# AirU_PoE.net
KiCad netlist of a schematic drawn in EAGLE
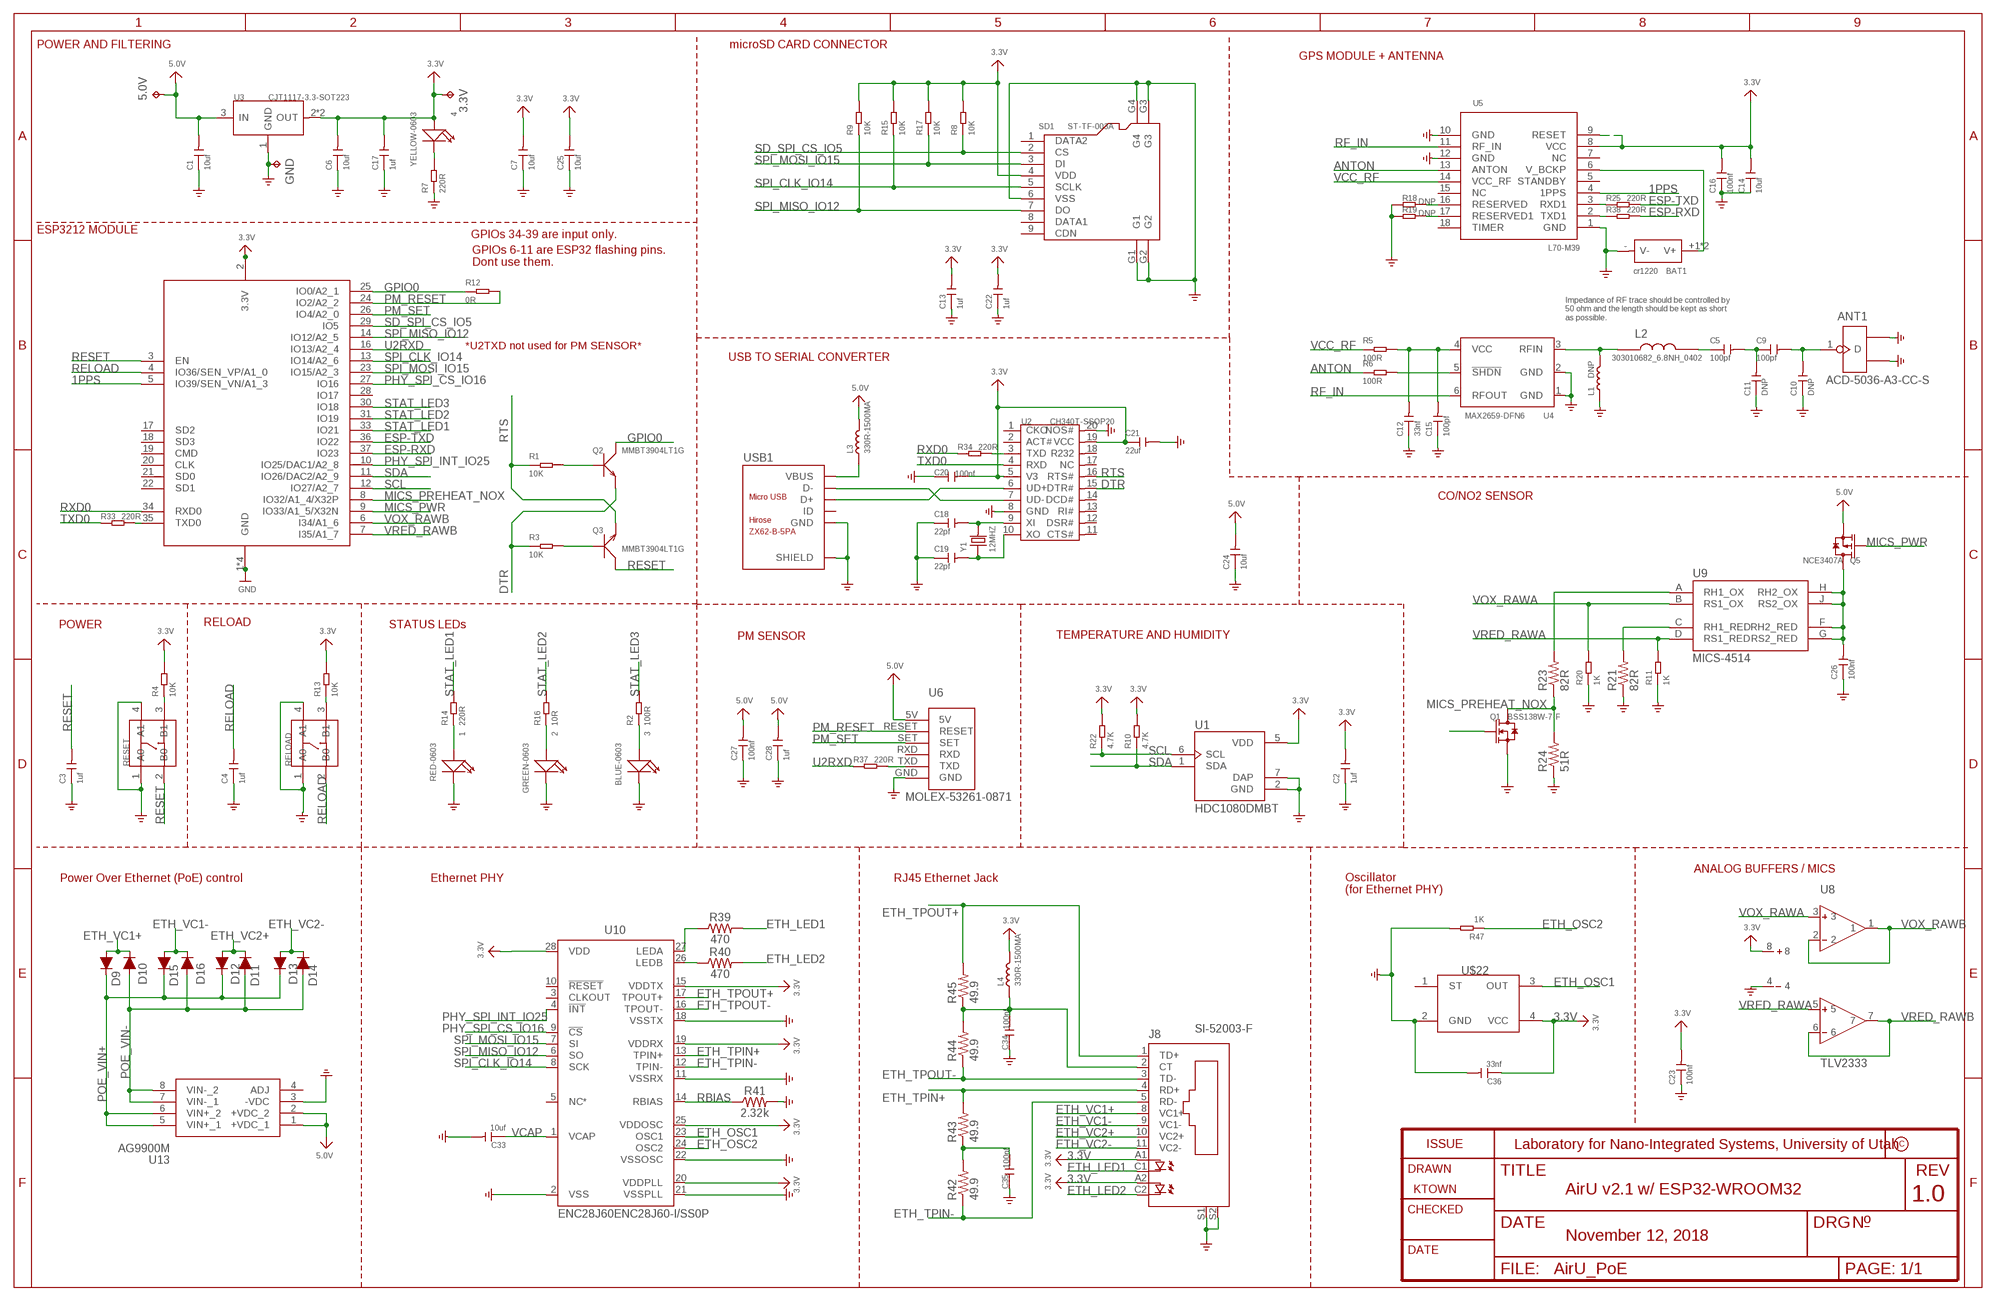
[diagram p0: schematic, sheet 1]

(export (version "E")
  (design (tool "Eeschema 10.0.6"))
  (components
    (comp (ref "1")
      (value "RED-0603")
      (footprint "eagle-import:LED-0603")
      (fields (field (name "MPN") "19-217-R6C-AL1M2VY-3T"))
      (libsource (lib "eagle-import") (part "LED-SMD-RED-DIFFUSED(0603)"))
    )
    (comp (ref "2")
      (value "GREEN-0603")
      (footprint "eagle-import:LED-0603")
      (fields (field (name "MPN") "19-217-G7C-AN1P2-3T"))
      (libsource (lib "eagle-import") (part "SMD-LED-CLEAR-GREEN(0603)"))
    )
    (comp (ref "3")
      (value "BLUE-0603")
      (footprint "eagle-import:LED-0603")
      (fields (field (name "MPN") "19-217-BHC-ZL1M2RY-3T"))
      (libsource (lib "eagle-import") (part "SMD-LED-CLEAR-BLUE(0603)"))
    )
    (comp (ref "3.3V")
      (value "TPTP20SQ")
      (footprint "eagle-import:TP20SQ")
      (libsource (lib "eagle-import") (part "TPTP20SQ"))
    )
    (comp (ref "4")
      (value "YELLOW-0603")
      (footprint "eagle-import:LED-0603")
      (fields (field (name "MPN") "19-217-Y5C-AM1N1VY-3T"))
      (libsource (lib "eagle-import") (part "SMD-LED-CLEAR-YELLOW(0603)"))
    )
    (comp (ref "5.0V")
      (value "TPTP20SQ")
      (footprint "eagle-import:TP20SQ")
      (libsource (lib "eagle-import") (part "TPTP20SQ"))
    )
    (comp (ref "ANT1")
      (value "ACD-5036-A3-CC-S")
      (footprint "eagle-import:ANT3-SMD-5.2X3.7X0.7MM")
      (libsource (lib "eagle-import") (part "ANTENNA-ACD5036"))
    )
    (comp (ref "BAT1")
      (value "cr1220")
      (footprint "eagle-import:BAT2P-13.5-CR1220")
      (libsource (lib "eagle-import") (part "DIP-BATTERY-CELL-HOLDER(1220)"))
    )
    (comp (ref "C1")
      (value "10uf")
      (footprint "eagle-import:C0603")
      (fields (field (name "MPN") "CC0603KRX5R6BB106"))
      (libsource (lib "eagle-import") (part "CERAMIC-10UF-10V-10%-X5R(0603)"))
    )
    (comp (ref "C2")
      (value "1uf")
      (footprint "eagle-import:C0603")
      (fields (field (name "MPN") "CC0603KRX7R8BB105"))
      (libsource (lib "eagle-import") (part "CERAMIC-1UF-25V-10%-X7R(0603)"))
    )
    (comp (ref "C3")
      (value "1uf")
      (footprint "eagle-import:C0603")
      (fields (field (name "MPN") "CC0603KRX7R8BB105"))
      (libsource (lib "eagle-import") (part "CERAMIC-1UF-25V-10%-X7R(0603)"))
    )
    (comp (ref "C4")
      (value "1uf")
      (footprint "eagle-import:C0603")
      (fields (field (name "MPN") "CC0603KRX7R8BB105"))
      (libsource (lib "eagle-import") (part "CERAMIC-1UF-25V-10%-X7R(0603)"))
    )
    (comp (ref "C5")
      (value "100pf")
      (footprint "eagle-import:C0603")
      (fields (field (name "MPN") "CC0603JRNPO9BN101"))
      (libsource (lib "eagle-import") (part "CERAMIC-100PF-50V-5%-NPO(0603)"))
    )
    (comp (ref "C6")
      (value "10uf")
      (footprint "eagle-import:C0603")
      (fields (field (name "MPN") "CC0603KRX5R6BB106"))
      (libsource (lib "eagle-import") (part "CERAMIC-10UF-10V-10%-X5R(0603)"))
    )
    (comp (ref "C7")
      (value "10uf")
      (footprint "eagle-import:C0603")
      (fields (field (name "MPN") "CC0603KRX5R6BB106"))
      (libsource (lib "eagle-import") (part "CERAMIC-10UF-10V-10%-X5R(0603)"))
    )
    (comp (ref "C9")
      (value "100pf")
      (footprint "eagle-import:C0603")
      (fields (field (name "MPN") "CC0603JRNPO9BN101"))
      (libsource (lib "eagle-import") (part "CERAMIC-100PF-50V-5%-NPO(0603)"))
    )
    (comp (ref "C10")
      (value "DNP")
      (footprint "eagle-import:C0603")
      (fields (field (name "MPN") "CC0603JRNPO9BN101"))
      (libsource (lib "eagle-import") (part "CERAMIC-100PF-50V-5%-NPO(0603)"))
    )
    (comp (ref "C11")
      (value "DNP")
      (footprint "eagle-import:C0603")
      (fields (field (name "MPN") "CC0603JRNPO9BN101"))
      (libsource (lib "eagle-import") (part "CERAMIC-100PF-50V-5%-NPO(0603)"))
    )
    (comp (ref "C12")
      (value "33nf")
      (footprint "eagle-import:C0603")
      (fields (field (name "MPN") "CC0603KRX7R9BB333"))
      (libsource (lib "eagle-import") (part "CERAMIC-33NF-50V-10%-X7R(0603)"))
    )
    (comp (ref "C13")
      (value "1uf")
      (footprint "eagle-import:C0603")
      (fields (field (name "MPN") "CC0603KRX7R8BB105"))
      (libsource (lib "eagle-import") (part "CERAMIC-1UF-25V-10%-X7R(0603)"))
    )
    (comp (ref "C14")
      (value "10uf")
      (footprint "eagle-import:C0603")
      (fields (field (name "MPN") "CC0603KRX5R6BB106"))
      (libsource (lib "eagle-import") (part "CERAMIC-10UF-10V-10%-X5R(0603)"))
    )
    (comp (ref "C15")
      (value "100pf")
      (footprint "eagle-import:C0603")
      (fields (field (name "MPN") "CC0603JRNPO9BN101"))
      (libsource (lib "eagle-import") (part "CERAMIC-100PF-50V-5%-NPO(0603)"))
    )
    (comp (ref "C16")
      (value "100nf")
      (footprint "eagle-import:C0603")
      (fields (field (name "MPN") "CC0603KRX7R9BB104"))
      (libsource (lib "eagle-import") (part "CERAMIC-100NF-50V-10%-X7R(0603)"))
    )
    (comp (ref "C17")
      (value "1uf")
      (footprint "eagle-import:C0603")
      (fields (field (name "MPN") "CC0603KRX7R8BB105"))
      (libsource (lib "eagle-import") (part "CERAMIC-1UF-25V-10%-X7R(0603)"))
    )
    (comp (ref "C18")
      (value "22pf")
      (footprint "eagle-import:C0603")
      (fields (field (name "MPN") "CC0603JRNPO9BN220"))
      (libsource (lib "eagle-import") (part "CERAMIC-22PF-50V-5%-NPO(0603)"))
    )
    (comp (ref "C19")
      (value "22pf")
      (footprint "eagle-import:C0603")
      (fields (field (name "MPN") "CC0603JRNPO9BN220"))
      (libsource (lib "eagle-import") (part "CERAMIC-22PF-50V-5%-NPO(0603)"))
    )
    (comp (ref "C20")
      (value "100nf")
      (footprint "eagle-import:C0603")
      (fields (field (name "MPN") "CC0603KRX7R9BB104"))
      (libsource (lib "eagle-import") (part "CERAMIC-100NF-50V-10%-X7R(0603)"))
    )
    (comp (ref "C21")
      (value "22uf")
      (footprint "eagle-import:C0805")
      (fields (field (name "MPN") "CC0805MKX5R5BB226"))
      (libsource (lib "eagle-import") (part "CERAMIC-22UF-6.3V-20%-X5R(0805)"))
    )
    (comp (ref "C22")
      (value "1uf")
      (footprint "eagle-import:C0603")
      (fields (field (name "MPN") "CC0603KRX7R8BB105"))
      (libsource (lib "eagle-import") (part "CERAMIC-1UF-25V-10%-X7R(0603)"))
    )
    (comp (ref "C23")
      (value "100nf")
      (footprint "eagle-import:C0603")
      (fields (field (name "MPN") "CC0603KRX7R9BB104"))
      (libsource (lib "eagle-import") (part "CERAMIC-100NF-50V-10%-X7R(0603)"))
    )
    (comp (ref "C24")
      (value "10uf")
      (footprint "eagle-import:C0603")
      (fields (field (name "MPN") "CC0603KRX5R6BB106"))
      (libsource (lib "eagle-import") (part "CERAMIC-10UF-10V-10%-X5R(0603)"))
    )
    (comp (ref "C25")
      (value "10uf")
      (footprint "eagle-import:C0603")
      (fields (field (name "MPN") "CC0603KRX5R6BB106"))
      (libsource (lib "eagle-import") (part "CERAMIC-10UF-10V-10%-X5R(0603)"))
    )
    (comp (ref "C26")
      (value "100nf")
      (footprint "eagle-import:C0603")
      (fields (field (name "MPN") "CC0603KRX7R9BB104"))
      (libsource (lib "eagle-import") (part "CERAMIC-100NF-50V-10%-X7R(0603)"))
    )
    (comp (ref "C27")
      (value "100nf")
      (footprint "eagle-import:C0603")
      (fields (field (name "MPN") "CC0603KRX7R9BB104"))
      (libsource (lib "eagle-import") (part "CERAMIC-100NF-50V-10%-X7R(0603)"))
    )
    (comp (ref "C28")
      (value "1uf")
      (footprint "eagle-import:C0603")
      (fields (field (name "MPN") "CC0603KRX7R8BB105"))
      (libsource (lib "eagle-import") (part "CERAMIC-1UF-25V-10%-X7R(0603)"))
    )
    (comp (ref "C33")
      (value "10uf")
      (footprint "eagle-import:C0603")
      (fields (field (name "MPN") "CC0603KRX5R6BB106"))
      (libsource (lib "eagle-import") (part "CERAMIC-10UF-10V-10%-X5R(0603)"))
    )
    (comp (ref "C34")
      (value "100nf")
      (footprint "eagle-import:C0603")
      (fields (field (name "MPN") "CC0603KRX7R9BB104"))
      (libsource (lib "eagle-import") (part "CERAMIC-100NF-50V-10%-X7R(0603)"))
    )
    (comp (ref "C35")
      (value "100nf")
      (footprint "eagle-import:C0603")
      (fields (field (name "MPN") "CC0603KRX7R9BB104"))
      (libsource (lib "eagle-import") (part "CERAMIC-100NF-50V-10%-X7R(0603)"))
    )
    (comp (ref "C36")
      (value "33nf")
      (footprint "eagle-import:C0603")
      (fields (field (name "MPN") "CC0603KRX7R9BB333"))
      (libsource (lib "eagle-import") (part "CERAMIC-33NF-50V-10%-X7R(0603)"))
    )
    (comp (ref "D9")
      (value "250mA/100V")
      (footprint "eagle-import:SOD-323")
      (libsource (lib "eagle-import") (part "DIODE-BAS16J"))
    )
    (comp (ref "D10")
      (value "250mA/100V")
      (footprint "eagle-import:SOD-323")
      (libsource (lib "eagle-import") (part "DIODE-BAS16J"))
    )
    (comp (ref "D11")
      (value "250mA/100V")
      (footprint "eagle-import:SOD-323")
      (libsource (lib "eagle-import") (part "DIODE-BAS16J"))
    )
    (comp (ref "D12")
      (value "250mA/100V")
      (footprint "eagle-import:SOD-323")
      (libsource (lib "eagle-import") (part "DIODE-BAS16J"))
    )
    (comp (ref "D13")
      (value "250mA/100V")
      (footprint "eagle-import:SOD-323")
      (libsource (lib "eagle-import") (part "DIODE-BAS16J"))
    )
    (comp (ref "D14")
      (value "250mA/100V")
      (footprint "eagle-import:SOD-323")
      (libsource (lib "eagle-import") (part "DIODE-BAS16J"))
    )
    (comp (ref "D15")
      (value "250mA/100V")
      (footprint "eagle-import:SOD-323")
      (libsource (lib "eagle-import") (part "DIODE-BAS16J"))
    )
    (comp (ref "D16")
      (value "250mA/100V")
      (footprint "eagle-import:SOD-323")
      (libsource (lib "eagle-import") (part "DIODE-BAS16J"))
    )
    (comp (ref "GND")
      (value "TPTP20SQ")
      (footprint "eagle-import:TP20SQ")
      (libsource (lib "eagle-import") (part "TPTP20SQ"))
    )
    (comp (ref "J8")
      (value "SI-52003-F")
      (footprint "eagle-import:SI-52003-F")
      (fields (field (name "MF") "Stewart Connector"))
      (libsource (lib "eagle-import") (part "SI-52003-F"))
    )
    (comp (ref "L1")
      (value "DNP")
      (footprint "eagle-import:L0201")
      (libsource (lib "eagle-import") (part "INDUCTOR/FERRITE-BEAD-0201"))
    )
    (comp (ref "L2")
      (value "303010682_6.8NH_0402")
      (footprint "eagle-import:L0402")
      (libsource (lib "eagle-import") (part "303010682_6.8NH_0402"))
    )
    (comp (ref "L3")
      (value "330R-1500MA")
      (footprint "eagle-import:L0805")
      (fields (field (name "MPN") "BLM21PG331SN1D"))
      (libsource (lib "eagle-import") (part "SMD-FERRITE-BEAD-330R-1500MA(0805)'0805'"))
    )
    (comp (ref "L4")
      (value "330R-1500MA")
      (footprint "eagle-import:L0805")
      (fields (field (name "MPN") "BLM21PG331SN1D"))
      (libsource (lib "eagle-import") (part "SMD-FERRITE-BEAD-330R-1500MA(0805)'0805'"))
    )
    (comp (ref "Q1")
      (value "BSS138W-7-F")
      (footprint "eagle-import:SOT-23")
      (libsource (lib "eagle-import") (part "SMD-MOSFET-N-CH-50V-200MA-BSS138W-7-F(SOT-23)"))
    )
    (comp (ref "Q2")
      (value "MMBT3904LT1G")
      (footprint "eagle-import:SOT-23")
      (libsource (lib "eagle-import") (part "SMD-TRANSISTORS-NPN-40V-200MA-MMBT3904LT1G(SOT-23)"))
    )
    (comp (ref "Q3")
      (value "MMBT3904LT1G")
      (footprint "eagle-import:SOT-23")
      (libsource (lib "eagle-import") (part "SMD-TRANSISTORS-NPN-40V-200MA-MMBT3904LT1G(SOT-23)"))
    )
    (comp (ref "Q5")
      (value "NCE3407A")
      (footprint "eagle-import:SOT-23")
      (libsource (lib "eagle-import") (part "SMD-MOSFET-P-CH-VDC=30V-ID=4.3A-NCE3407A(SOT-23)"))
    )
    (comp (ref "R1")
      (value "10K")
      (footprint "eagle-import:R0603")
      (fields (field (name "MPN") "RC0603FR-0710KL"))
      (libsource (lib "eagle-import") (part "SMD-RES-10K-1%-1/10W(0603)"))
    )
    (comp (ref "R2")
      (value "100R")
      (footprint "eagle-import:R0603")
      (fields (field (name "MPN") "RC0603JR-07100RL"))
      (libsource (lib "eagle-import") (part "SMD-RES-100R-5%-1/10W(0603)"))
    )
    (comp (ref "R3")
      (value "10K")
      (footprint "eagle-import:R0603")
      (fields (field (name "MPN") "RC0603FR-0710KL"))
      (libsource (lib "eagle-import") (part "SMD-RES-10K-1%-1/10W(0603)"))
    )
    (comp (ref "R4")
      (value "10K")
      (footprint "eagle-import:R0603")
      (fields (field (name "MPN") "RC0603FR-0710KL"))
      (libsource (lib "eagle-import") (part "SMD-RES-10K-1%-1/10W(0603)"))
    )
    (comp (ref "R5")
      (value "100R")
      (footprint "eagle-import:R0603")
      (fields (field (name "MPN") "RC0603JR-07100RL"))
      (libsource (lib "eagle-import") (part "SMD-RES-100R-5%-1/10W(0603)"))
    )
    (comp (ref "R6")
      (value "100R")
      (footprint "eagle-import:R0603")
      (fields (field (name "MPN") "RC0603JR-07100RL"))
      (libsource (lib "eagle-import") (part "SMD-RES-100R-5%-1/10W(0603)"))
    )
    (comp (ref "R7")
      (value "220R")
      (footprint "eagle-import:R0603")
      (fields (field (name "MPN") "RC0603JR-07220RL"))
      (libsource (lib "eagle-import") (part "SMD-RES-220R-5%-1/10W(0603)"))
    )
    (comp (ref "R8")
      (value "10K")
      (footprint "eagle-import:R0603")
      (fields (field (name "MPN") "RC0603FR-0710KL"))
      (libsource (lib "eagle-import") (part "SMD-RES-10K-1%-1/10W(0603)"))
    )
    (comp (ref "R9")
      (value "10K")
      (footprint "eagle-import:R0603")
      (fields (field (name "MPN") "RC0603FR-0710KL"))
      (libsource (lib "eagle-import") (part "SMD-RES-10K-1%-1/10W(0603)"))
    )
    (comp (ref "R10")
      (value "4.7K")
      (footprint "eagle-import:R0603")
      (fields (field (name "MPN") "RC0603JR-074K7L"))
      (libsource (lib "eagle-import") (part "SMD-RES-4.7K-5%-1/10W(0603)"))
    )
    (comp (ref "R11")
      (value "1K")
      (footprint "eagle-import:R0603")
      (fields (field (name "MPN") "RC0603FR-071KL"))
      (libsource (lib "eagle-import") (part "SMD-RES-1K-1%-1/10W(0603)"))
    )
    (comp (ref "R12")
      (value "0R")
      (footprint "eagle-import:R0603")
      (fields (field (name "MPN") "RC0603JR-070RL"))
      (libsource (lib "eagle-import") (part "SMD-RES-0R-5%-1/10W(0603)"))
    )
    (comp (ref "R13")
      (value "10K")
      (footprint "eagle-import:R0603")
      (fields (field (name "MPN") "RC0603FR-0710KL"))
      (libsource (lib "eagle-import") (part "SMD-RES-10K-1%-1/10W(0603)"))
    )
    (comp (ref "R14")
      (value "220R")
      (footprint "eagle-import:R0603")
      (fields (field (name "MPN") "RC0603JR-07220RL"))
      (libsource (lib "eagle-import") (part "SMD-RES-220R-5%-1/10W(0603)"))
    )
    (comp (ref "R15")
      (value "10K")
      (footprint "eagle-import:R0603")
      (fields (field (name "MPN") "RC0603FR-0710KL"))
      (libsource (lib "eagle-import") (part "SMD-RES-10K-1%-1/10W(0603)"))
    )
    (comp (ref "R16")
      (value "10R")
      (footprint "eagle-import:R0603")
      (fields (field (name "MPN") "RC0603JR-0710RL"))
      (libsource (lib "eagle-import") (part "SMD-RES-10R-5%-1/10W(0603)"))
    )
    (comp (ref "R17")
      (value "10K")
      (footprint "eagle-import:R0603")
      (fields (field (name "MPN") "RC0603FR-0710KL"))
      (libsource (lib "eagle-import") (part "SMD-RES-10K-1%-1/10W(0603)"))
    )
    (comp (ref "R18")
      (value "DNP")
      (footprint "eagle-import:R0603")
      (fields (field (name "MPN") "RC0603FR-0710KL"))
      (libsource (lib "eagle-import") (part "SMD-RES-10K-1%-1/10W(0603)"))
    )
    (comp (ref "R19")
      (value "DNP")
      (footprint "eagle-import:R0603")
      (fields (field (name "MPN") "RC0603FR-0710KL"))
      (libsource (lib "eagle-import") (part "SMD-RES-10K-1%-1/10W(0603)"))
    )
    (comp (ref "R20")
      (value "1K")
      (footprint "eagle-import:R0603")
      (fields (field (name "MPN") "RC0603FR-071KL"))
      (libsource (lib "eagle-import") (part "SMD-RES-1K-1%-1/10W(0603)"))
    )
    (comp (ref "R21")
      (value "82R")
      (footprint "eagle-import:R0603")
      (libsource (lib "eagle-import") (part "rcl_334_R-US_R0603"))
    )
    (comp (ref "R22")
      (value "4.7K")
      (footprint "eagle-import:R0603")
      (fields (field (name "MPN") "RC0603JR-074K7L"))
      (libsource (lib "eagle-import") (part "SMD-RES-4.7K-5%-1/10W(0603)"))
    )
    (comp (ref "R23")
      (value "82R")
      (footprint "eagle-import:R0603")
      (libsource (lib "eagle-import") (part "rcl_334_R-US_R0603"))
    )
    (comp (ref "R24")
      (value "51R")
      (footprint "eagle-import:R0603")
      (libsource (lib "eagle-import") (part "rcl_334_R-US_R0603"))
    )
    (comp (ref "R25")
      (value "220R")
      (footprint "eagle-import:R0603")
      (fields (field (name "MPN") "RC0603JR-07220RL"))
      (libsource (lib "eagle-import") (part "SMD-RES-220R-5%-1/10W(0603)"))
    )
    (comp (ref "R33")
      (value "220R")
      (footprint "eagle-import:R0603")
      (fields (field (name "MPN") "RC0603JR-07220RL"))
      (libsource (lib "eagle-import") (part "SMD-RES-220R-5%-1/10W(0603)"))
    )
    (comp (ref "R34")
      (value "220R")
      (footprint "eagle-import:R0603")
      (fields (field (name "MPN") "RC0603JR-07220RL"))
      (libsource (lib "eagle-import") (part "SMD-RES-220R-5%-1/10W(0603)"))
    )
    (comp (ref "R37")
      (value "220R")
      (footprint "eagle-import:R0603")
      (fields (field (name "MPN") "RC0603JR-07220RL"))
      (libsource (lib "eagle-import") (part "SMD-RES-220R-5%-1/10W(0603)"))
    )
    (comp (ref "R38")
      (value "220R")
      (footprint "eagle-import:R0603")
      (fields (field (name "MPN") "RC0603JR-07220RL"))
      (libsource (lib "eagle-import") (part "SMD-RES-220R-5%-1/10W(0603)"))
    )
    (comp (ref "R39")
      (value "470")
      (footprint "eagle-import:0603")
      (libsource (lib "eagle-import") (part "470OHM-0603-1/10W-1%"))
    )
    (comp (ref "R40")
      (value "470")
      (footprint "eagle-import:0603")
      (libsource (lib "eagle-import") (part "470OHM-0603-1/10W-1%"))
    )
    (comp (ref "R41")
      (value "2.32k")
      (footprint "eagle-import:0603")
      (libsource (lib "eagle-import") (part "2.2KOHM-0603-1/10W-1%"))
    )
    (comp (ref "R42")
      (value "49.9")
      (footprint "eagle-import:M0805")
      (libsource (lib "eagle-import") (part "R-US_M0805"))
    )
    (comp (ref "R43")
      (value "49.9")
      (footprint "eagle-import:M0805")
      (libsource (lib "eagle-import") (part "R-US_M0805"))
    )
    (comp (ref "R44")
      (value "49.9")
      (footprint "eagle-import:M0805")
      (libsource (lib "eagle-import") (part "R-US_M0805"))
    )
    (comp (ref "R45")
      (value "49.9")
      (footprint "eagle-import:M0805")
      (libsource (lib "eagle-import") (part "R-US_M0805"))
    )
    (comp (ref "R47")
      (value "1K")
      (footprint "eagle-import:R0603")
      (fields (field (name "MPN") "RC0603FR-071KL"))
      (libsource (lib "eagle-import") (part "SMD-RES-1K-1%-1/10W(0603)"))
    )
    (comp (ref "RELOAD")
      (value "DIP-SWITCH-TACTILE-SPST-NO/TS-1109(4P-D6.0MM)'TS-1109'")
      (footprint "eagle-import:SW4-6.0X6.0X5.0MM")
      (libsource (lib "eagle-import") (part "DIP-SWITCH-TACTILE-SPST-NO/TS-1109(4P-D6.0MM)'TS-1109'"))
    )
    (comp (ref "RESET")
      (value "DIP-SWITCH-TACTILE-SPST-NO/TS-1109(4P-D6.0MM)'TS-1109'")
      (footprint "eagle-import:SW4-6.0X6.0X5.0MM")
      (libsource (lib "eagle-import") (part "DIP-SWITCH-TACTILE-SPST-NO/TS-1109(4P-D6.0MM)'TS-1109'"))
    )
    (comp (ref "SD1")
      (value "ST-TF-003A")
      (footprint "eagle-import:MICRO-SD9+4P-SMD-16.1X14.5X1.85MM")
      (libsource (lib "eagle-import") (part "MICRO-SD-CARD-SOCKET-9P(ST-TF-003A)"))
    )
    (comp (ref "U$22")
      (value "SPXO25MHZ7050-4P")
      (footprint "eagle-import:DFN700X500X150-4N")
      (libsource (lib "eagle-import") (part "SPXO25MHZ7050-4P"))
    )
    (comp (ref "U1")
      (value "HDC1080DMBT")
      (footprint "eagle-import:SON100P300X300X80-7N")
      (fields (field (name "DIGI-KEY_PART_NUMBER") "296-43864-1-ND") (field (name "MF") "Texas Instruments"))
      (libsource (lib "eagle-import") (part "HDC1080DMBT"))
    )
    (comp (ref "U2")
      (value "CH340T-SSOP20")
      (footprint "eagle-import:SSOP20-0.65-7.6X5.2MM")
      (fields (field (name "MPN") "CH340T"))
      (libsource (lib "eagle-import") (part "INTERFACE-CH340T(SSOP20)"))
    )
    (comp (ref "U3")
      (value "CJT1117-3.3-SOT223")
      (footprint "eagle-import:SOT-223")
      (fields (field (name "MPN") "CJT1117-3.3"))
      (libsource (lib "eagle-import") (part "PMIC-CJT1117-3.3(SOT223)"))
    )
    (comp (ref "U4")
      (value "MAX2659-DFN6")
      (footprint "eagle-import:DFN6-0.5-1.5X1.2X0.72MM")
      (fields (field (name "MPN") "MAX2659"))
      (libsource (lib "eagle-import") (part "AMPLIFIER-MAX2659"))
    )
    (comp (ref "U5")
      (value "L70-M39")
      (footprint "eagle-import:LGA18-1.1-9.7X10.1X2.5MM")
      (fields (field (name "MPN") "L70"))
      (libsource (lib "eagle-import") (part "MOUDLE-GPS-L70-HARDWARE"))
    )
    (comp (ref "U6")
      (value "MOLEX-53261-0871")
      (footprint "eagle-import:MOLEX-53261-0871")
      (libsource (lib "eagle-import") (part "MOLEX-53261-0871"))
    )
    (comp (ref "U7")
      (value "ESP32_WROOM32_SKINNY")
      (footprint "eagle-import:WROOM32_SKINNY")
      (libsource (lib "eagle-import") (part "ESP32_WROOM32_SKINNY"))
    )
    (comp (ref "U8")
      (value "TLV2333")
      (footprint "eagle-import:TLV2333")
      (libsource (lib "eagle-import") (part "TLV2333"))
    )
    (comp (ref "U9")
      (value "MICS-4514")
      (footprint "eagle-import:MICS_10-SMD")
      (fields (field (name "MF") "Amphenol"))
      (libsource (lib "eagle-import") (part "MICS-4514"))
    )
    (comp (ref "U10")
      (value "ENC28J60ENC28J60-I/SS0P")
      (footprint "eagle-import:SOP65P780X200-28")
      (libsource (lib "eagle-import") (part "ENC28J60ENC28J60-I/SS0P"))
    )
    (comp (ref "U13")
      (value "AG9900M")
      (footprint "eagle-import:AG9900M")
      (fields (field (name "MANUFACTURER_PART_NUMBER") "Ag9900M"))
      (libsource (lib "eagle-import") (part "AG9900M"))
    )
    (comp (ref "USB1")
      (value "ZX62-B-5PA")
      (footprint "eagle-import:MICRO-USB5+6P-SMD-0.65-AB")
      (libsource (lib "eagle-import") (part "MICRO-USB-SMD(ZX62-B-5PA)"))
    )
    (comp (ref "Y1")
      (value "12MHZ")
      (footprint "eagle-import:X2-SMD-5.0X3.2X1.3MM")
      (fields (field (name "MPN") "5032/2P"))
      (libsource (lib "eagle-import") (part "SMD-CRYSTAL-12MHZ-20PF-20PPM-40R(2P-5.0X3.2MM)"))
    )
  )
  (nets
    (net (code "1") (name "/1PPS") (class "Default")
      (node (ref "U5") (pin "4") (pinfunction "1PPS_4") (pintype "bidirectional"))
      (node (ref "U7") (pin "5") (pinfunction "IO39/SEN_VN/A1_3_5") (pintype "passive"))
    )
    (net (code "2") (name "/ANTON") (class "Default")
      (node (ref "R6") (pin "1") (pinfunction "1_1") (pintype "passive"))
      (node (ref "U5") (pin "13") (pinfunction "ANTON_13") (pintype "bidirectional"))
    )
    (net (code "3") (name "/DTR") (class "Default")
      (node (ref "Q2") (pin "2") (pinfunction "E_2") (pintype "passive"))
      (node (ref "R3") (pin "1") (pinfunction "1_1") (pintype "passive"))
      (node (ref "U2") (pin "15") (pinfunction "DTR#_15") (pintype "output"))
    )
    (net (code "4") (name "/ESP-RXD") (class "Default")
      (node (ref "R38") (pin "2") (pinfunction "2_2") (pintype "passive"))
      (node (ref "U7") (pin "37") (pinfunction "IO23_37") (pintype "bidirectional"))
    )
    (net (code "5") (name "/ESP-TXD") (class "Default")
      (node (ref "R25") (pin "2") (pinfunction "2_2") (pintype "passive"))
      (node (ref "U7") (pin "36") (pinfunction "IO22_36") (pintype "bidirectional"))
    )
    (net (code "6") (name "/ETH_LED1") (class "Default")
      (node (ref "J8") (pin "C1") (pinfunction "C1_C1") (pintype "passive"))
      (node (ref "R39") (pin "2") (pinfunction "2_2") (pintype "passive"))
    )
    (net (code "7") (name "/ETH_LED2") (class "Default")
      (node (ref "J8") (pin "C2") (pinfunction "C2_C2") (pintype "passive"))
      (node (ref "R40") (pin "2") (pinfunction "2_2") (pintype "passive"))
    )
    (net (code "8") (name "/ETH_OSC1") (class "Default")
      (node (ref "U$22") (pin "3") (pinfunction "OUT_3") (pintype "bidirectional"))
      (node (ref "U10") (pin "23") (pinfunction "OSC1_23") (pintype "input"))
    )
    (net (code "9") (name "/ETH_OSC2") (class "Default")
      (node (ref "R47") (pin "1") (pinfunction "1_1") (pintype "passive"))
      (node (ref "U10") (pin "24") (pinfunction "OSC2_24") (pintype "output"))
    )
    (net (code "10") (name "/ETH_TPIN+") (class "Default")
      (node (ref "J8") (pin "4") (pinfunction "RD+_4") (pintype "passive"))
      (node (ref "R43") (pin "2") (pinfunction "2_2") (pintype "passive"))
      (node (ref "U10") (pin "13") (pinfunction "TPIN+_13") (pintype "input"))
    )
    (net (code "11") (name "/ETH_TPIN-") (class "Default")
      (node (ref "J8") (pin "5") (pinfunction "RD-_5") (pintype "passive"))
      (node (ref "R42") (pin "1") (pinfunction "1_1") (pintype "passive"))
      (node (ref "U10") (pin "12") (pinfunction "TPIN-_12") (pintype "input"))
    )
    (net (code "12") (name "/ETH_TPOUT+") (class "Default")
      (node (ref "J8") (pin "1") (pinfunction "TD+_1") (pintype "passive"))
      (node (ref "R45") (pin "2") (pinfunction "2_2") (pintype "passive"))
      (node (ref "U10") (pin "17") (pinfunction "TPOUT+_17") (pintype "output"))
    )
    (net (code "13") (name "/ETH_TPOUT-") (class "Default")
      (node (ref "J8") (pin "3") (pinfunction "TD-_3") (pintype "passive"))
      (node (ref "R44") (pin "1") (pinfunction "1_1") (pintype "passive"))
      (node (ref "U10") (pin "16") (pinfunction "TPOUT-_16") (pintype "output"))
    )
    (net (code "14") (name "/ETH_VC1+") (class "Default")
      (node (ref "D10") (pin "C") (pinfunction "C_C") (pintype "passive"))
      (node (ref "D9") (pin "A") (pinfunction "A_A") (pintype "passive"))
      (node (ref "J8") (pin "8") (pinfunction "VC1+_8") (pintype "passive"))
    )
    (net (code "15") (name "/ETH_VC1-") (class "Default")
      (node (ref "D15") (pin "A") (pinfunction "A_A") (pintype "passive"))
      (node (ref "D16") (pin "C") (pinfunction "C_C") (pintype "passive"))
      (node (ref "J8") (pin "9") (pinfunction "VC1-_9") (pintype "passive"))
    )
    (net (code "16") (name "/ETH_VC2+") (class "Default")
      (node (ref "D11") (pin "C") (pinfunction "C_C") (pintype "passive"))
      (node (ref "D12") (pin "A") (pinfunction "A_A") (pintype "passive"))
      (node (ref "J8") (pin "10") (pinfunction "VC2+_10") (pintype "passive"))
    )
    (net (code "17") (name "/ETH_VC2-") (class "Default")
      (node (ref "D13") (pin "A") (pinfunction "A_A") (pintype "passive"))
      (node (ref "D14") (pin "C") (pinfunction "C_C") (pintype "passive"))
      (node (ref "J8") (pin "11") (pinfunction "VC2-_11") (pintype "bidirectional"))
    )
    (net (code "18") (name "/GPIO0") (class "Default")
      (node (ref "Q2") (pin "3") (pinfunction "C_3") (pintype "passive"))
      (node (ref "R12") (pin "1") (pinfunction "1_1") (pintype "passive"))
      (node (ref "U7") (pin "25") (pinfunction "IO0/A2_1_25") (pintype "bidirectional"))
    )
    (net (code "19") (name "/MICS_PREHEAT_NOX") (class "Default")
      (node (ref "Q1") (pin "1") (pinfunction "G_1") (pintype "passive"))
      (node (ref "U7") (pin "8") (pinfunction "IO32/A1_4/X32P_8") (pintype "bidirectional"))
    )
    (net (code "20") (name "/MICS_PWR") (class "Default")
      (node (ref "Q5") (pin "1") (pinfunction "G_1") (pintype "passive"))
      (node (ref "U7") (pin "9") (pinfunction "IO33/A1_5/X32N_9") (pintype "bidirectional"))
    )
    (net (code "21") (name "/PHY_SPI_CS_IO16") (class "Default")
      (node (ref "U10") (pin "9") (pinfunction "~{CS}_9") (pintype "input"))
      (node (ref "U7") (pin "27") (pinfunction "IO16_27") (pintype "bidirectional"))
    )
    (net (code "22") (name "/PHY_SPI_INT_IO25") (class "Default")
      (node (ref "U10") (pin "4") (pinfunction "~{INT}_4") (pintype "output"))
      (node (ref "U7") (pin "10") (pinfunction "IO25/DAC1/A2_8_10") (pintype "bidirectional"))
    )
    (net (code "23") (name "/PM_RESET") (class "Default")
      (node (ref "R12") (pin "2") (pinfunction "2_2") (pintype "passive"))
      (node (ref "U6") (pin "RESET") (pinfunction "RESET_RESET") (pintype "bidirectional"))
      (node (ref "U7") (pin "24") (pinfunction "IO2/A2_2_24") (pintype "bidirectional"))
    )
    (net (code "24") (name "/PM_SET") (class "Default")
      (node (ref "U6") (pin "SET") (pinfunction "SET_SET") (pintype "bidirectional"))
      (node (ref "U7") (pin "26") (pinfunction "IO4/A2_0_26") (pintype "bidirectional"))
    )
    (net (code "25") (name "/POE_VIN+") (class "Default")
      (node (ref "D12") (pin "C") (pinfunction "C_C") (pintype "passive"))
      (node (ref "D13") (pin "C") (pinfunction "C_C") (pintype "passive"))
      (node (ref "D15") (pin "C") (pinfunction "C_C") (pintype "passive"))
      (node (ref "D9") (pin "C") (pinfunction "C_C") (pintype "passive"))
      (node (ref "U13") (pin "5") (pinfunction "VIN+_1_5") (pintype "bidirectional"))
      (node (ref "U13") (pin "6") (pinfunction "VIN+_2_6") (pintype "bidirectional"))
    )
    (net (code "26") (name "/POE_VIN-") (class "Default")
      (node (ref "D10") (pin "A") (pinfunction "A_A") (pintype "passive"))
      (node (ref "D11") (pin "A") (pinfunction "A_A") (pintype "passive"))
      (node (ref "D14") (pin "A") (pinfunction "A_A") (pintype "passive"))
      (node (ref "D16") (pin "A") (pinfunction "A_A") (pintype "passive"))
      (node (ref "U13") (pin "7") (pinfunction "VIN-_1_7") (pintype "bidirectional"))
      (node (ref "U13") (pin "8") (pinfunction "VIN-_2_8") (pintype "bidirectional"))
    )
    (net (code "27") (name "/RBIAS") (class "Default")
      (node (ref "R41") (pin "1") (pinfunction "1_1") (pintype "passive"))
      (node (ref "U10") (pin "14") (pinfunction "RBIAS_14") (pintype "input"))
    )
    (net (code "28") (name "/RELOAD") (class "Default")
      (node (ref "C4") (pin "2") (pinfunction "2_2") (pintype "passive"))
      (node (ref "RELOAD") (pin "2") (pinfunction "B0_2") (pintype "bidirectional"))
      (node (ref "U7") (pin "4") (pinfunction "IO36/SEN_VP/A1_0_4") (pintype "passive"))
    )
    (net (code "29") (name "/RESET") (class "Default")
      (node (ref "C3") (pin "2") (pinfunction "2_2") (pintype "passive"))
      (node (ref "Q3") (pin "3") (pinfunction "C_3") (pintype "passive"))
      (node (ref "RESET") (pin "2") (pinfunction "B0_2") (pintype "bidirectional"))
      (node (ref "U7") (pin "3") (pinfunction "EN_3") (pintype "input"))
    )
    (net (code "30") (name "/RF_IN") (class "Default")
      (node (ref "U4") (pin "6") (pinfunction "RFOUT_6") (pintype "bidirectional"))
      (node (ref "U5") (pin "11") (pinfunction "RF_IN_11") (pintype "bidirectional"))
    )
    (net (code "31") (name "/RTS") (class "Default")
      (node (ref "Q3") (pin "2") (pinfunction "E_2") (pintype "passive"))
      (node (ref "R1") (pin "1") (pinfunction "1_1") (pintype "passive"))
      (node (ref "U2") (pin "16") (pinfunction "RTS#_16") (pintype "output"))
    )
    (net (code "32") (name "/RXD0") (class "Default")
      (node (ref "R34") (pin "1") (pinfunction "1_1") (pintype "passive"))
      (node (ref "U7") (pin "34") (pinfunction "RXD0_34") (pintype "input"))
    )
    (net (code "33") (name "/SCL") (class "Default")
      (node (ref "R22") (pin "1") (pinfunction "1_1") (pintype "passive"))
      (node (ref "U1") (pin "6") (pinfunction "SCL_6") (pintype "input"))
      (node (ref "U7") (pin "12") (pinfunction "IO27/A2_7_12") (pintype "bidirectional"))
    )
    (net (code "34") (name "/SDA") (class "Default")
      (node (ref "R10") (pin "1") (pinfunction "1_1") (pintype "passive"))
      (node (ref "U1") (pin "1") (pinfunction "SDA_1") (pintype "bidirectional"))
      (node (ref "U7") (pin "11") (pinfunction "IO26/DAC2/A2_9_11") (pintype "bidirectional"))
    )
    (net (code "35") (name "/SD_SPI_CS_IO5") (class "Default")
      (node (ref "R8") (pin "1") (pinfunction "1_1") (pintype "passive"))
      (node (ref "SD1") (pin "2") (pinfunction "CS_2") (pintype "bidirectional"))
      (node (ref "U7") (pin "29") (pinfunction "IO5_29") (pintype "bidirectional"))
    )
    (net (code "36") (name "/SPI_CLK_IO14") (class "Default")
      (node (ref "R15") (pin "1") (pinfunction "1_1") (pintype "passive"))
      (node (ref "SD1") (pin "5") (pinfunction "SCLK_5") (pintype "bidirectional"))
      (node (ref "U10") (pin "8") (pinfunction "SCK_8") (pintype "input"))
      (node (ref "U7") (pin "13") (pinfunction "IO14/A2_6_13") (pintype "bidirectional"))
    )
    (net (code "37") (name "/SPI_MISO_IO12") (class "Default")
      (node (ref "R9") (pin "1") (pinfunction "1_1") (pintype "passive"))
      (node (ref "SD1") (pin "7") (pinfunction "DO_7") (pintype "bidirectional"))
      (node (ref "U10") (pin "6") (pinfunction "SO_6") (pintype "output"))
      (node (ref "U7") (pin "14") (pinfunction "IO12/A2_5_14") (pintype "bidirectional"))
    )
    (net (code "38") (name "/SPI_MOSI_IO15") (class "Default")
      (node (ref "R17") (pin "1") (pinfunction "1_1") (pintype "passive"))
      (node (ref "SD1") (pin "3") (pinfunction "DI_3") (pintype "bidirectional"))
      (node (ref "U10") (pin "7") (pinfunction "SI_7") (pintype "input"))
      (node (ref "U7") (pin "23") (pinfunction "IO15/A2_3_23") (pintype "bidirectional"))
    )
    (net (code "39") (name "/STAT_LED1") (class "Default")
      (node (ref "R14") (pin "2") (pinfunction "2_2") (pintype "passive"))
      (node (ref "U7") (pin "33") (pinfunction "IO21_33") (pintype "bidirectional"))
    )
    (net (code "40") (name "/STAT_LED2") (class "Default")
      (node (ref "R16") (pin "2") (pinfunction "2_2") (pintype "passive"))
      (node (ref "U7") (pin "31") (pinfunction "IO19_31") (pintype "bidirectional"))
    )
    (net (code "41") (name "/STAT_LED3") (class "Default")
      (node (ref "R2") (pin "2") (pinfunction "2_2") (pintype "passive"))
      (node (ref "U7") (pin "30") (pinfunction "IO18_30") (pintype "bidirectional"))
    )
    (net (code "42") (name "/TXD0") (class "Default")
      (node (ref "R33") (pin "1") (pinfunction "1_1") (pintype "passive"))
      (node (ref "U2") (pin "4") (pinfunction "RXD_4") (pintype "input"))
    )
    (net (code "43") (name "/U2RXD") (class "Default")
      (node (ref "R37") (pin "1") (pinfunction "1_1") (pintype "passive"))
      (node (ref "U7") (pin "16") (pinfunction "IO13/A2_4_16") (pintype "bidirectional"))
    )
    (net (code "44") (name "/VCAP") (class "Default")
      (node (ref "C33") (pin "1") (pinfunction "1_1") (pintype "passive"))
      (node (ref "U10") (pin "1") (pinfunction "VCAP_1") (pintype "input"))
    )
    (net (code "45") (name "/VCC_RF") (class "Default")
      (node (ref "R5") (pin "1") (pinfunction "1_1") (pintype "passive"))
      (node (ref "U5") (pin "14") (pinfunction "VCC_RF_14") (pintype "power_in"))
    )
    (net (code "46") (name "/VOX_RAWA") (class "Default")
      (node (ref "R20") (pin "2") (pinfunction "2_2") (pintype "passive"))
      (node (ref "U8") (pin "3") (pinfunction "3_3") (pintype "bidirectional"))
      (node (ref "U9") (pin "B") (pinfunction "RS1_OX_B") (pintype "bidirectional"))
    )
    (net (code "47") (name "/VOX_RAWB") (class "Default")
      (node (ref "U7") (pin "6") (pinfunction "I34/A1_6_6") (pintype "bidirectional"))
      (node (ref "U8") (pin "1") (pinfunction "1_1") (pintype "bidirectional"))
      (node (ref "U8") (pin "2") (pinfunction "2_2") (pintype "bidirectional"))
    )
    (net (code "48") (name "/VRED_RAWA") (class "Default")
      (node (ref "R11") (pin "2") (pinfunction "2_2") (pintype "passive"))
      (node (ref "U8") (pin "5") (pinfunction "5_5") (pintype "bidirectional"))
      (node (ref "U9") (pin "D") (pinfunction "RS1_RED_D") (pintype "bidirectional"))
    )
    (net (code "49") (name "/VRED_RAWB") (class "Default")
      (node (ref "U7") (pin "7") (pinfunction "I35/A1_7_7") (pintype "bidirectional"))
      (node (ref "U8") (pin "6") (pinfunction "6_6") (pintype "bidirectional"))
      (node (ref "U8") (pin "7") (pinfunction "7_7") (pintype "bidirectional"))
    )
    (net (code "50") (name "3.3V") (class "Default")
      (node (ref "3.3V") (pin "TP") (pinfunction "TP_TP") (pintype "input"))
      (node (ref "4") (pin "+") (pinfunction "+_+") (pintype "passive"))
      (node (ref "C13") (pin "2") (pinfunction "2_2") (pintype "passive"))
      (node (ref "C14") (pin "2") (pinfunction "2_2") (pintype "passive"))
      (node (ref "C16") (pin "2") (pinfunction "2_2") (pintype "passive"))
      (node (ref "C17") (pin "2") (pinfunction "2_2") (pintype "passive"))
      (node (ref "C2") (pin "2") (pinfunction "2_2") (pintype "passive"))
      (node (ref "C20") (pin "2") (pinfunction "2_2") (pintype "passive"))
      (node (ref "C21") (pin "1") (pinfunction "1_1") (pintype "passive"))
      (node (ref "C22") (pin "2") (pinfunction "2_2") (pintype "passive"))
      (node (ref "C23") (pin "2") (pinfunction "2_2") (pintype "passive"))
      (node (ref "C25") (pin "2") (pinfunction "2_2") (pintype "passive"))
      (node (ref "C36") (pin "1") (pinfunction "1_1") (pintype "passive"))
      (node (ref "C6") (pin "2") (pinfunction "2_2") (pintype "passive"))
      (node (ref "C7") (pin "2") (pinfunction "2_2") (pintype "passive"))
      (node (ref "J8") (pin "A1") (pinfunction "A1_A1") (pintype "passive"))
      (node (ref "J8") (pin "A2") (pinfunction "A2_A2") (pintype "passive"))
      (node (ref "L4") (pin "2") (pinfunction "2_2") (pintype "passive"))
      (node (ref "R10") (pin "2") (pinfunction "2_2") (pintype "passive"))
      (node (ref "R13") (pin "2") (pinfunction "2_2") (pintype "passive"))
      (node (ref "R15") (pin "2") (pinfunction "2_2") (pintype "passive"))
      (node (ref "R17") (pin "2") (pinfunction "2_2") (pintype "passive"))
      (node (ref "R22") (pin "2") (pinfunction "2_2") (pintype "passive"))
      (node (ref "R4") (pin "2") (pinfunction "2_2") (pintype "passive"))
      (node (ref "R8") (pin "2") (pinfunction "2_2") (pintype "passive"))
      (node (ref "R9") (pin "2") (pinfunction "2_2") (pintype "passive"))
      (node (ref "SD1") (pin "4") (pinfunction "VDD_4") (pintype "bidirectional"))
      (node (ref "U$22") (pin "4") (pinfunction "VCC_4") (pintype "bidirectional"))
      (node (ref "U1") (pin "5") (pinfunction "VDD_5") (pintype "power_in"))
      (node (ref "U10") (pin "15") (pinfunction "VDDTX_15") (pintype "input"))
      (node (ref "U10") (pin "19") (pinfunction "VDDRX_19") (pintype "input"))
      (node (ref "U10") (pin "20") (pinfunction "VDDPLL_20") (pintype "input"))
      (node (ref "U10") (pin "25") (pinfunction "VDDOSC_25") (pintype "input"))
      (node (ref "U10") (pin "28") (pinfunction "VDD_28") (pintype "input"))
      (node (ref "U2") (pin "19") (pinfunction "VCC_19") (pintype "power_in"))
      (node (ref "U2") (pin "5") (pinfunction "V3_5") (pintype "power_in"))
      (node (ref "U3") (pin "2") (pinfunction "OUT_2") (pintype "bidirectional"))
      (node (ref "U3") (pin "TER") (pinfunction "OUT_TER") (pintype "bidirectional"))
      (node (ref "U5") (pin "8") (pinfunction "VCC_8") (pintype "power_in"))
      (node (ref "U5") (pin "9") (pinfunction "RESET_9") (pintype "bidirectional"))
      (node (ref "U7") (pin "2") (pinfunction "3.3V_2") (pintype "passive"))
      (node (ref "U8") (pin "8") (pinfunction "8_8") (pintype "bidirectional"))
    )
    (net (code "51") (name "5.0V") (class "Default")
      (node (ref "5.0V") (pin "TP") (pinfunction "TP_TP") (pintype "input"))
      (node (ref "C1") (pin "2") (pinfunction "2_2") (pintype "passive"))
      (node (ref "C24") (pin "2") (pinfunction "2_2") (pintype "passive"))
      (node (ref "C27") (pin "2") (pinfunction "2_2") (pintype "passive"))
      (node (ref "C28") (pin "2") (pinfunction "2_2") (pintype "passive"))
      (node (ref "L3") (pin "2") (pinfunction "2_2") (pintype "passive"))
      (node (ref "Q5") (pin "2") (pinfunction "S_2") (pintype "passive"))
      (node (ref "U13") (pin "1") (pinfunction "+VDC_1_1") (pintype "bidirectional"))
      (node (ref "U13") (pin "2") (pinfunction "+VDC_2_2") (pintype "bidirectional"))
      (node (ref "U3") (pin "3") (pinfunction "IN_3") (pintype "bidirectional"))
      (node (ref "U6") (pin "5V") (pinfunction "5V_5V") (pintype "bidirectional"))
    )
    (net (code "52") (name "GND") (class "Default")
      (node (ref "1") (pin "-") (pinfunction "-_-") (pintype "passive"))
      (node (ref "2") (pin "-") (pinfunction "-_-") (pintype "passive"))
      (node (ref "3") (pin "-") (pinfunction "-_-") (pintype "passive"))
      (node (ref "ANT1") (pin "2") (pinfunction "GND1_2") (pintype "bidirectional"))
      (node (ref "ANT1") (pin "3") (pinfunction "GND2_3") (pintype "bidirectional"))
      (node (ref "BAT1") (pin "-") (pinfunction "V-_-") (pintype "bidirectional"))
      (node (ref "C1") (pin "1") (pinfunction "1_1") (pintype "passive"))
      (node (ref "C10") (pin "1") (pinfunction "1_1") (pintype "passive"))
      (node (ref "C11") (pin "1") (pinfunction "1_1") (pintype "passive"))
      (node (ref "C12") (pin "1") (pinfunction "1_1") (pintype "passive"))
      (node (ref "C13") (pin "1") (pinfunction "1_1") (pintype "passive"))
      (node (ref "C14") (pin "1") (pinfunction "1_1") (pintype "passive"))
      (node (ref "C15") (pin "1") (pinfunction "1_1") (pintype "passive"))
      (node (ref "C16") (pin "1") (pinfunction "1_1") (pintype "passive"))
      (node (ref "C17") (pin "1") (pinfunction "1_1") (pintype "passive"))
      (node (ref "C18") (pin "1") (pinfunction "1_1") (pintype "passive"))
      (node (ref "C19") (pin "1") (pinfunction "1_1") (pintype "passive"))
      (node (ref "C2") (pin "1") (pinfunction "1_1") (pintype "passive"))
      (node (ref "C20") (pin "1") (pinfunction "1_1") (pintype "passive"))
      (node (ref "C21") (pin "2") (pinfunction "2_2") (pintype "passive"))
      (node (ref "C22") (pin "1") (pinfunction "1_1") (pintype "passive"))
      (node (ref "C23") (pin "1") (pinfunction "1_1") (pintype "passive"))
      (node (ref "C24") (pin "1") (pinfunction "1_1") (pintype "passive"))
      (node (ref "C25") (pin "1") (pinfunction "1_1") (pintype "passive"))
      (node (ref "C26") (pin "1") (pinfunction "1_1") (pintype "passive"))
      (node (ref "C27") (pin "1") (pinfunction "1_1") (pintype "passive"))
      (node (ref "C28") (pin "1") (pinfunction "1_1") (pintype "passive"))
      (node (ref "C3") (pin "1") (pinfunction "1_1") (pintype "passive"))
      (node (ref "C33") (pin "2") (pinfunction "2_2") (pintype "passive"))
      (node (ref "C34") (pin "1") (pinfunction "1_1") (pintype "passive"))
      (node (ref "C35") (pin "1") (pinfunction "1_1") (pintype "passive"))
      (node (ref "C36") (pin "2") (pinfunction "2_2") (pintype "passive"))
      (node (ref "C4") (pin "1") (pinfunction "1_1") (pintype "passive"))
      (node (ref "C6") (pin "1") (pinfunction "1_1") (pintype "passive"))
      (node (ref "C7") (pin "1") (pinfunction "1_1") (pintype "passive"))
      (node (ref "GND") (pin "TP") (pinfunction "TP_TP") (pintype "input"))
      (node (ref "J8") (pin "S1") (pinfunction "S1_S1") (pintype "passive"))
      (node (ref "J8") (pin "S2") (pinfunction "S2_S2") (pintype "passive"))
      (node (ref "L1") (pin "1") (pinfunction "1_1") (pintype "passive"))
      (node (ref "Q1") (pin "2") (pinfunction "S_2") (pintype "passive"))
      (node (ref "R11") (pin "1") (pinfunction "1_1") (pintype "passive"))
      (node (ref "R18") (pin "1") (pinfunction "1_1") (pintype "passive"))
      (node (ref "R19") (pin "1") (pinfunction "1_1") (pintype "passive"))
      (node (ref "R20") (pin "1") (pinfunction "1_1") (pintype "passive"))
      (node (ref "R21") (pin "1") (pinfunction "1_1") (pintype "passive"))
      (node (ref "R24") (pin "1") (pinfunction "1_1") (pintype "passive"))
      (node (ref "R41") (pin "2") (pinfunction "2_2") (pintype "passive"))
      (node (ref "R47") (pin "2") (pinfunction "2_2") (pintype "passive"))
      (node (ref "R7") (pin "1") (pinfunction "1_1") (pintype "passive"))
      (node (ref "RELOAD") (pin "1") (pinfunction "A0_1") (pintype "bidirectional"))
      (node (ref "RELOAD") (pin "4") (pinfunction "A1_4") (pintype "bidirectional"))
      (node (ref "RESET") (pin "1") (pinfunction "A0_1") (pintype "bidirectional"))
      (node (ref "RESET") (pin "4") (pinfunction "A1_4") (pintype "bidirectional"))
      (node (ref "SD1") (pin "6") (pinfunction "VSS_6") (pintype "bidirectional"))
      (node (ref "SD1") (pin "G1") (pinfunction "G1_G1") (pintype "bidirectional"))
      (node (ref "SD1") (pin "G2") (pinfunction "G2_G2") (pintype "bidirectional"))
      (node (ref "SD1") (pin "G3") (pinfunction "G3_G3") (pintype "bidirectional"))
      (node (ref "SD1") (pin "G4") (pinfunction "G4_G4") (pintype "bidirectional"))
      (node (ref "U$22") (pin "2") (pinfunction "GND_2") (pintype "bidirectional"))
      (node (ref "U1") (pin "2") (pinfunction "GND_2") (pintype "power_in"))
      (node (ref "U1") (pin "7") (pinfunction "DAP_7") (pintype "power_in"))
      (node (ref "U10") (pin "11") (pinfunction "VSSRX_11") (pintype "input"))
      (node (ref "U10") (pin "18") (pinfunction "VSSTX_18") (pintype "input"))
      (node (ref "U10") (pin "2") (pinfunction "VSS_2") (pintype "input"))
      (node (ref "U10") (pin "21") (pinfunction "VSSPLL_21") (pintype "input"))
      (node (ref "U10") (pin "22") (pinfunction "VSSOSC_22") (pintype "input"))
      (node (ref "U13") (pin "3") (pinfunction "-VDC_3") (pintype "bidirectional"))
      (node (ref "U2") (pin "20") (pinfunction "NOS#_20") (pintype "power_in"))
      (node (ref "U2") (pin "8") (pinfunction "GND_8") (pintype "power_in"))
      (node (ref "U3") (pin "1") (pinfunction "GND_1") (pintype "bidirectional"))
      (node (ref "U4") (pin "1") (pinfunction "GND_1") (pintype "power_in"))
      (node (ref "U4") (pin "2") (pinfunction "GND_2") (pintype "power_in"))
      (node (ref "U5") (pin "1") (pinfunction "GND_1") (pintype "power_in"))
      (node (ref "U5") (pin "10") (pinfunction "GND_10") (pintype "power_in"))
      (node (ref "U5") (pin "12") (pinfunction "GND_12") (pintype "bidirectional"))
      (node (ref "U6") (pin "GND") (pinfunction "GND_GND") (pintype "bidirectional"))
      (node (ref "U7") (pin "1") (pinfunction "GND_1") (pintype "passive"))
      (node (ref "U7") (pin "15") (pinfunction "GND_15") (pintype "passive"))
      (node (ref "U7") (pin "38") (pinfunction "GND_38") (pintype "passive"))
      (node (ref "U7") (pin "P$1") (pinfunction "GND_P$1") (pintype "passive"))
      (node (ref "U8") (pin "4") (pinfunction "4_4") (pintype "bidirectional"))
      (node (ref "USB1") (pin "5") (pinfunction "GND_5") (pintype "power_in"))
      (node (ref "USB1") (pin "P1") (pinfunction "SHIELD_P1") (pintype "power_in"))
      (node (ref "USB1") (pin "P2") (pinfunction "SHIELD_P2") (pintype "power_in"))
      (node (ref "USB1") (pin "P3_1") (pinfunction "SHIELD_P3_1") (pintype "power_in"))
      (node (ref "USB1") (pin "P3_2") (pinfunction "SHIELD_P3_2") (pintype "power_in"))
      (node (ref "USB1") (pin "P3_3") (pinfunction "SHIELD_P3_3") (pintype "power_in"))
      (node (ref "USB1") (pin "P4_1") (pinfunction "SHIELD_P4_1") (pintype "power_in"))
      (node (ref "USB1") (pin "P4_2") (pinfunction "SHIELD_P4_2") (pintype "power_in"))
      (node (ref "USB1") (pin "P4_3") (pinfunction "SHIELD_P4_3") (pintype "power_in"))
      (node (ref "USB1") (pin "P5") (pinfunction "SHIELD_P5") (pintype "power_in"))
      (node (ref "USB1") (pin "P6") (pinfunction "SHIELD_P6") (pintype "power_in"))
    )
    (net (code "53") (name "Net-(1-Pad+)") (class "Default")
      (node (ref "1") (pin "+") (pinfunction "+_+") (pintype "passive"))
      (node (ref "R14") (pin "1") (pinfunction "1_1") (pintype "passive"))
    )
    (net (code "54") (name "Net-(2-Pad+)") (class "Default")
      (node (ref "2") (pin "+") (pinfunction "+_+") (pintype "passive"))
      (node (ref "R16") (pin "1") (pinfunction "1_1") (pintype "passive"))
    )
    (net (code "55") (name "Net-(3-Pad+)") (class "Default")
      (node (ref "3") (pin "+") (pinfunction "+_+") (pintype "passive"))
      (node (ref "R2") (pin "1") (pinfunction "1_1") (pintype "passive"))
    )
    (net (code "56") (name "Net-(4-Pad-)") (class "Default")
      (node (ref "4") (pin "-") (pinfunction "-_-") (pintype "passive"))
      (node (ref "R7") (pin "2") (pinfunction "2_2") (pintype "passive"))
    )
    (net (code "57") (name "Net-(ANT1-D)") (class "Default")
      (node (ref "ANT1") (pin "1") (pinfunction "D_1") (pintype "bidirectional"))
      (node (ref "C10") (pin "2") (pinfunction "2_2") (pintype "passive"))
      (node (ref "C9") (pin "2") (pinfunction "2_2") (pintype "passive"))
    )
    (net (code "58") (name "Net-(C5-Pad1)") (class "Default")
      (node (ref "C5") (pin "1") (pinfunction "1_1") (pintype "passive"))
      (node (ref "L2") (pin "P$2") (pinfunction "P$2_P$2") (pintype "passive"))
    )
    (net (code "59") (name "Net-(C11-Pad2)") (class "Default")
      (node (ref "C11") (pin "2") (pinfunction "2_2") (pintype "passive"))
      (node (ref "C5") (pin "2") (pinfunction "2_2") (pintype "passive"))
      (node (ref "C9") (pin "1") (pinfunction "1_1") (pintype "passive"))
    )
    (net (code "60") (name "Net-(C35-Pad2)") (class "Default")
      (node (ref "C35") (pin "2") (pinfunction "2_2") (pintype "passive"))
      (node (ref "R42") (pin "2") (pinfunction "2_2") (pintype "passive"))
      (node (ref "R43") (pin "1") (pinfunction "1_1") (pintype "passive"))
    )
    (net (code "61") (name "Net-(J8-CT)") (class "Default")
      (node (ref "C34") (pin "2") (pinfunction "2_2") (pintype "passive"))
      (node (ref "J8") (pin "2") (pinfunction "CT_2") (pintype "passive"))
      (node (ref "L4") (pin "1") (pinfunction "1_1") (pintype "passive"))
      (node (ref "R44") (pin "2") (pinfunction "2_2") (pintype "passive"))
      (node (ref "R45") (pin "1") (pinfunction "1_1") (pintype "passive"))
    )
    (net (code "62") (name "Net-(Q1-D)") (class "Default")
      (node (ref "Q1") (pin "3") (pinfunction "D_3") (pintype "passive"))
      (node (ref "R23") (pin "1") (pinfunction "1_1") (pintype "passive"))
      (node (ref "R24") (pin "2") (pinfunction "2_2") (pintype "passive"))
    )
    (net (code "63") (name "Net-(Q2-B)") (class "Default")
      (node (ref "Q2") (pin "1") (pinfunction "B_1") (pintype "passive"))
      (node (ref "R1") (pin "2") (pinfunction "2_2") (pintype "passive"))
    )
    (net (code "64") (name "Net-(Q3-B)") (class "Default")
      (node (ref "Q3") (pin "1") (pinfunction "B_1") (pintype "passive"))
      (node (ref "R3") (pin "2") (pinfunction "2_2") (pintype "passive"))
    )
    (net (code "65") (name "Net-(Q5-D)") (class "Default")
      (node (ref "C26") (pin "2") (pinfunction "2_2") (pintype "passive"))
      (node (ref "Q5") (pin "3") (pinfunction "D_3") (pintype "passive"))
      (node (ref "U9") (pin "F") (pinfunction "RH2_RED_F") (pintype "bidirectional"))
      (node (ref "U9") (pin "G") (pinfunction "RS2_RED_G") (pintype "bidirectional"))
      (node (ref "U9") (pin "H") (pinfunction "RH2_OX_H") (pintype "bidirectional"))
      (node (ref "U9") (pin "J") (pinfunction "RS2_OX_J") (pintype "bidirectional"))
    )
    (net (code "66") (name "Net-(R37-Pad2)") (class "Default")
      (node (ref "R37") (pin "2") (pinfunction "2_2") (pintype "passive"))
      (node (ref "U6") (pin "TXD") (pinfunction "TXD_TXD") (pintype "bidirectional"))
    )
    (net (code "67") (name "Net-(RELOAD-B1)") (class "Default")
      (node (ref "R13") (pin "1") (pinfunction "1_1") (pintype "passive"))
      (node (ref "RELOAD") (pin "3") (pinfunction "B1_3") (pintype "bidirectional"))
    )
    (net (code "68") (name "Net-(RESET-B1)") (class "Default")
      (node (ref "R4") (pin "1") (pinfunction "1_1") (pintype "passive"))
      (node (ref "RESET") (pin "3") (pinfunction "B1_3") (pintype "bidirectional"))
    )
    (net (code "69") (name "Net-(U2-TXD)") (class "Default")
      (node (ref "R34") (pin "2") (pinfunction "2_2") (pintype "passive"))
      (node (ref "U2") (pin "3") (pinfunction "TXD_3") (pintype "output"))
    )
    (net (code "70") (name "Net-(U2-UD+)") (class "Default")
      (node (ref "U2") (pin "6") (pinfunction "UD+_6") (pintype "bidirectional"))
      (node (ref "USB1") (pin "3") (pinfunction "D+_3") (pintype "bidirectional"))
    )
    (net (code "71") (name "Net-(U2-UD-)") (class "Default")
      (node (ref "U2") (pin "7") (pinfunction "UD-_7") (pintype "bidirectional"))
      (node (ref "USB1") (pin "2") (pinfunction "D-_2") (pintype "bidirectional"))
    )
    (net (code "72") (name "Net-(U2-XI)") (class "Default")
      (node (ref "C18") (pin "2") (pinfunction "2_2") (pintype "passive"))
      (node (ref "U2") (pin "9") (pinfunction "XI_9") (pintype "input"))
      (node (ref "Y1") (pin "2") (pinfunction "2_2") (pintype "passive"))
    )
    (net (code "73") (name "Net-(U2-XO)") (class "Default")
      (node (ref "C19") (pin "2") (pinfunction "2_2") (pintype "passive"))
      (node (ref "U2") (pin "10") (pinfunction "XO_10") (pintype "output"))
      (node (ref "Y1") (pin "1") (pinfunction "1_1") (pintype "passive"))
    )
    (net (code "74") (name "Net-(U4-RFIN)") (class "Default")
      (node (ref "L1") (pin "2") (pinfunction "2_2") (pintype "passive"))
      (node (ref "L2") (pin "P$1") (pinfunction "P$1_P$1") (pintype "passive"))
      (node (ref "U4") (pin "3") (pinfunction "RFIN_3") (pintype "bidirectional"))
    )
    (net (code "75") (name "Net-(U4-VCC)") (class "Default")
      (node (ref "C12") (pin "2") (pinfunction "2_2") (pintype "passive"))
      (node (ref "C15") (pin "2") (pinfunction "2_2") (pintype "passive"))
      (node (ref "R5") (pin "2") (pinfunction "2_2") (pintype "passive"))
      (node (ref "U4") (pin "4") (pinfunction "VCC_4") (pintype "power_in"))
    )
    (net (code "76") (name "Net-(U4-~{SHDN})") (class "Default")
      (node (ref "R6") (pin "2") (pinfunction "2_2") (pintype "passive"))
      (node (ref "U4") (pin "5") (pinfunction "~{SHDN}_5") (pintype "bidirectional"))
    )
    (net (code "77") (name "Net-(U5-RESERVED)") (class "Default")
      (node (ref "R18") (pin "2") (pinfunction "2_2") (pintype "passive"))
      (node (ref "U5") (pin "16") (pinfunction "RESERVED_16") (pintype "bidirectional"))
    )
    (net (code "78") (name "Net-(U5-RESERVED1)") (class "Default")
      (node (ref "R19") (pin "2") (pinfunction "2_2") (pintype "passive"))
      (node (ref "U5") (pin "17") (pinfunction "RESERVED1_17") (pintype "bidirectional"))
    )
    (net (code "79") (name "Net-(U5-RXD1)") (class "Default")
      (node (ref "R25") (pin "1") (pinfunction "1_1") (pintype "passive"))
      (node (ref "U5") (pin "3") (pinfunction "RXD1_3") (pintype "bidirectional"))
    )
    (net (code "80") (name "Net-(U5-TXD1)") (class "Default")
      (node (ref "R38") (pin "1") (pinfunction "1_1") (pintype "passive"))
      (node (ref "U5") (pin "2") (pinfunction "TXD1_2") (pintype "bidirectional"))
    )
    (net (code "81") (name "Net-(U5-V_BCKP)") (class "Default")
      (node (ref "BAT1") (pin "+1") (pinfunction "V+_+1") (pintype "bidirectional"))
      (node (ref "BAT1") (pin "+2") (pinfunction "V+_+2") (pintype "bidirectional"))
      (node (ref "U5") (pin "6") (pinfunction "V_BCKP_6") (pintype "bidirectional"))
    )
    (net (code "82") (name "Net-(U7-TXD0)") (class "Default")
      (node (ref "R33") (pin "2") (pinfunction "2_2") (pintype "passive"))
      (node (ref "U7") (pin "35") (pinfunction "TXD0_35") (pintype "output"))
    )
    (net (code "83") (name "Net-(U9-RH1_OX)") (class "Default")
      (node (ref "R23") (pin "2") (pinfunction "2_2") (pintype "passive"))
      (node (ref "U9") (pin "A") (pinfunction "RH1_OX_A") (pintype "bidirectional"))
    )
    (net (code "84") (name "Net-(U9-RH1_RED)") (class "Default")
      (node (ref "R21") (pin "2") (pinfunction "2_2") (pintype "passive"))
      (node (ref "U9") (pin "C") (pinfunction "RH1_RED_C") (pintype "bidirectional"))
    )
    (net (code "85") (name "Net-(U10-LEDA)") (class "Default")
      (node (ref "R39") (pin "1") (pinfunction "1_1") (pintype "passive"))
      (node (ref "U10") (pin "27") (pinfunction "LEDA_27") (pintype "output"))
    )
    (net (code "86") (name "Net-(U10-LEDB)") (class "Default")
      (node (ref "R40") (pin "1") (pinfunction "1_1") (pintype "passive"))
      (node (ref "U10") (pin "26") (pinfunction "LEDB_26") (pintype "output"))
    )
    (net (code "87") (name "Net-(USB1-VBUS)") (class "Default")
      (node (ref "L3") (pin "1") (pinfunction "1_1") (pintype "passive"))
      (node (ref "USB1") (pin "1") (pinfunction "VBUS_1") (pintype "power_in"))
    )
    (net (code "88") (name "unconnected-(SD1-CDN-Pad9)") (class "Default")
      (node (ref "SD1") (pin "9") (pinfunction "CDN_9") (pintype "bidirectional"))
    )
    (net (code "89") (name "unconnected-(SD1-DATA1-Pad8)") (class "Default")
      (node (ref "SD1") (pin "8") (pinfunction "DATA1_8") (pintype "bidirectional"))
    )
    (net (code "90") (name "unconnected-(SD1-DATA2-Pad1)") (class "Default")
      (node (ref "SD1") (pin "1") (pinfunction "DATA2_1") (pintype "bidirectional"))
    )
    (net (code "91") (name "unconnected-(U$22-ST-Pad1)") (class "Default")
      (node (ref "U$22") (pin "1") (pinfunction "ST_1") (pintype "bidirectional"))
    )
    (net (code "92") (name "unconnected-(U2-ACT#-Pad2)") (class "Default")
      (node (ref "U2") (pin "2") (pinfunction "ACT#_2") (pintype "output"))
    )
    (net (code "93") (name "unconnected-(U2-CKO-Pad1)") (class "Default")
      (node (ref "U2") (pin "1") (pinfunction "CKO_1") (pintype "output"))
    )
    (net (code "94") (name "unconnected-(U2-CTS#-Pad11)") (class "Default")
      (node (ref "U2") (pin "11") (pinfunction "CTS#_11") (pintype "input"))
    )
    (net (code "95") (name "unconnected-(U2-DCD#-Pad14)") (class "Default")
      (node (ref "U2") (pin "14") (pinfunction "DCD#_14") (pintype "input"))
    )
    (net (code "96") (name "unconnected-(U2-DSR#-Pad12)") (class "Default")
      (node (ref "U2") (pin "12") (pinfunction "DSR#_12") (pintype "input"))
    )
    (net (code "97") (name "unconnected-(U2-NC-Pad17)") (class "Default")
      (node (ref "U2") (pin "17") (pinfunction "NC_17") (pintype "no_connect"))
    )
    (net (code "98") (name "unconnected-(U2-R232-Pad18)") (class "Default")
      (node (ref "U2") (pin "18") (pinfunction "R232_18") (pintype "input"))
    )
    (net (code "99") (name "unconnected-(U2-RI#-Pad13)") (class "Default")
      (node (ref "U2") (pin "13") (pinfunction "RI#_13") (pintype "input"))
    )
    (net (code "100") (name "unconnected-(U5-NC-Pad7)") (class "Default")
      (node (ref "U5") (pin "7") (pinfunction "NC_7") (pintype "bidirectional"))
    )
    (net (code "101") (name "unconnected-(U5-NC-Pad15)") (class "Default")
      (node (ref "U5") (pin "15") (pinfunction "NC_15") (pintype "bidirectional"))
    )
    (net (code "102") (name "unconnected-(U5-STANDBY-Pad5)") (class "Default")
      (node (ref "U5") (pin "5") (pinfunction "STANDBY_5") (pintype "bidirectional"))
    )
    (net (code "103") (name "unconnected-(U5-TIMER-Pad18)") (class "Default")
      (node (ref "U5") (pin "18") (pinfunction "TIMER_18") (pintype "bidirectional"))
    )
    (net (code "104") (name "unconnected-(U6-PadRXD)") (class "Default")
      (node (ref "U6") (pin "RXD") (pinfunction "RXD_RXD") (pintype "bidirectional"))
    )
    (net (code "105") (name "unconnected-(U7-CLK-Pad20)") (class "Default")
      (node (ref "U7") (pin "20") (pinfunction "CLK_20") (pintype "bidirectional"))
    )
    (net (code "106") (name "unconnected-(U7-CMD-Pad19)") (class "Default")
      (node (ref "U7") (pin "19") (pinfunction "CMD_19") (pintype "bidirectional"))
    )
    (net (code "107") (name "unconnected-(U7-IO17-Pad28)") (class "Default")
      (node (ref "U7") (pin "28") (pinfunction "IO17_28") (pintype "bidirectional"))
    )
    (net (code "108") (name "unconnected-(U7-SD0-Pad21)") (class "Default")
      (node (ref "U7") (pin "21") (pinfunction "SD0_21") (pintype "bidirectional"))
    )
    (net (code "109") (name "unconnected-(U7-SD1-Pad22)") (class "Default")
      (node (ref "U7") (pin "22") (pinfunction "SD1_22") (pintype "bidirectional"))
    )
    (net (code "110") (name "unconnected-(U7-SD2-Pad17)") (class "Default")
      (node (ref "U7") (pin "17") (pinfunction "SD2_17") (pintype "bidirectional"))
    )
    (net (code "111") (name "unconnected-(U7-SD3-Pad18)") (class "Default")
      (node (ref "U7") (pin "18") (pinfunction "SD3_18") (pintype "bidirectional"))
    )
    (net (code "112") (name "unconnected-(U10-CLKOUT-Pad3)") (class "Default")
      (node (ref "U10") (pin "3") (pinfunction "CLKOUT_3") (pintype "output"))
    )
    (net (code "113") (name "unconnected-(U10-NC*-Pad5)") (class "Default")
      (node (ref "U10") (pin "5") (pinfunction "NC*_5") (pintype "output"))
    )
    (net (code "114") (name "unconnected-(U10-~{RESET}-Pad10)") (class "Default")
      (node (ref "U10") (pin "10") (pinfunction "~{RESET}_10") (pintype "input"))
    )
    (net (code "115") (name "unconnected-(U13-ADJ-Pad4)") (class "Default")
      (node (ref "U13") (pin "4") (pinfunction "ADJ_4") (pintype "bidirectional"))
    )
    (net (code "116") (name "unconnected-(USB1-ID-Pad4)") (class "Default")
      (node (ref "USB1") (pin "4") (pinfunction "ID_4") (pintype "bidirectional"))
    )
  )
)
